# Power.net
KiCad netlist of a schematic drawn in Altium Designer
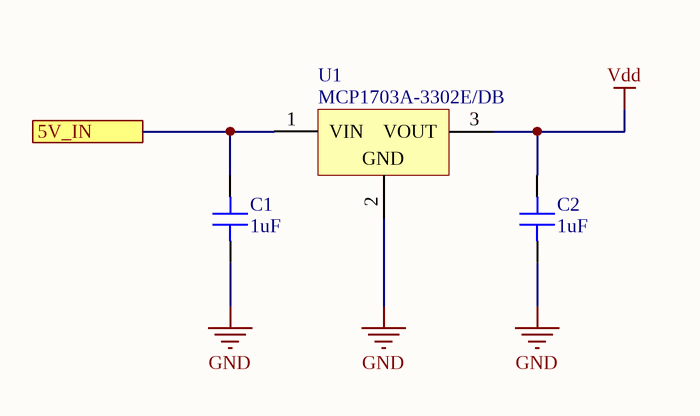
[diagram p0: Power.SchDoc]

(export (version "E")
  (design (tool "Eeschema 10.0.6"))
  (components
    (comp (ref "C1")
      (value "1uF")
      (footprint "CAP 0603_1608")
      (description "SMT Capacitor")
      (libsource (lib "SCH - PASSIVES - CAPACITOR") (part "Capacitor"))
    )
    (comp (ref "C2")
      (value "1uF")
      (footprint "CAP 0603_1608")
      (description "SMT Capacitor")
      (libsource (lib "SCH - PASSIVES - CAPACITOR") (part "Capacitor"))
    )
    (comp (ref "U1")
      (value "MCP1703A-3302E/DB")
      (footprint "MCHP-SOT-223-DB3_N")
      (description "250 mA, 16 V, Low Quiescent Current LDO Regulator, -40 to 125 degC, 3-pin SOT-223 (DB3), Tube")
      (fields (field (name "MANUFACTURER") "Microchip"))
      (libsource (lib "Altium Content Vault") (part "MCHP-MCP1703A-SOT-223-3"))
    )
  )
  (nets
    (net (code "1") (name "/5V_IN") (class "Default")
      (node (ref "C1") (pin "2") (pinfunction "2_2") (pintype "passive"))
      (node (ref "U1") (pin "1") (pinfunction "VIN_1") (pintype "power_in"))
    )
    (net (code "2") (name "GND") (class "Default")
      (node (ref "C1") (pin "1") (pinfunction "1_1") (pintype "passive"))
      (node (ref "C2") (pin "1") (pinfunction "1_1") (pintype "passive"))
      (node (ref "U1") (pin "2") (pinfunction "GND_2") (pintype "power_in"))
    )
    (net (code "3") (name "Vdd") (class "Default")
      (node (ref "C2") (pin "2") (pinfunction "2_2") (pintype "passive"))
      (node (ref "U1") (pin "3") (pinfunction "VOUT_3") (pintype "power_in"))
    )
  )
)
